# AT89S52-POV_Stick.net
KiCad netlist of a schematic drawn in EAGLE
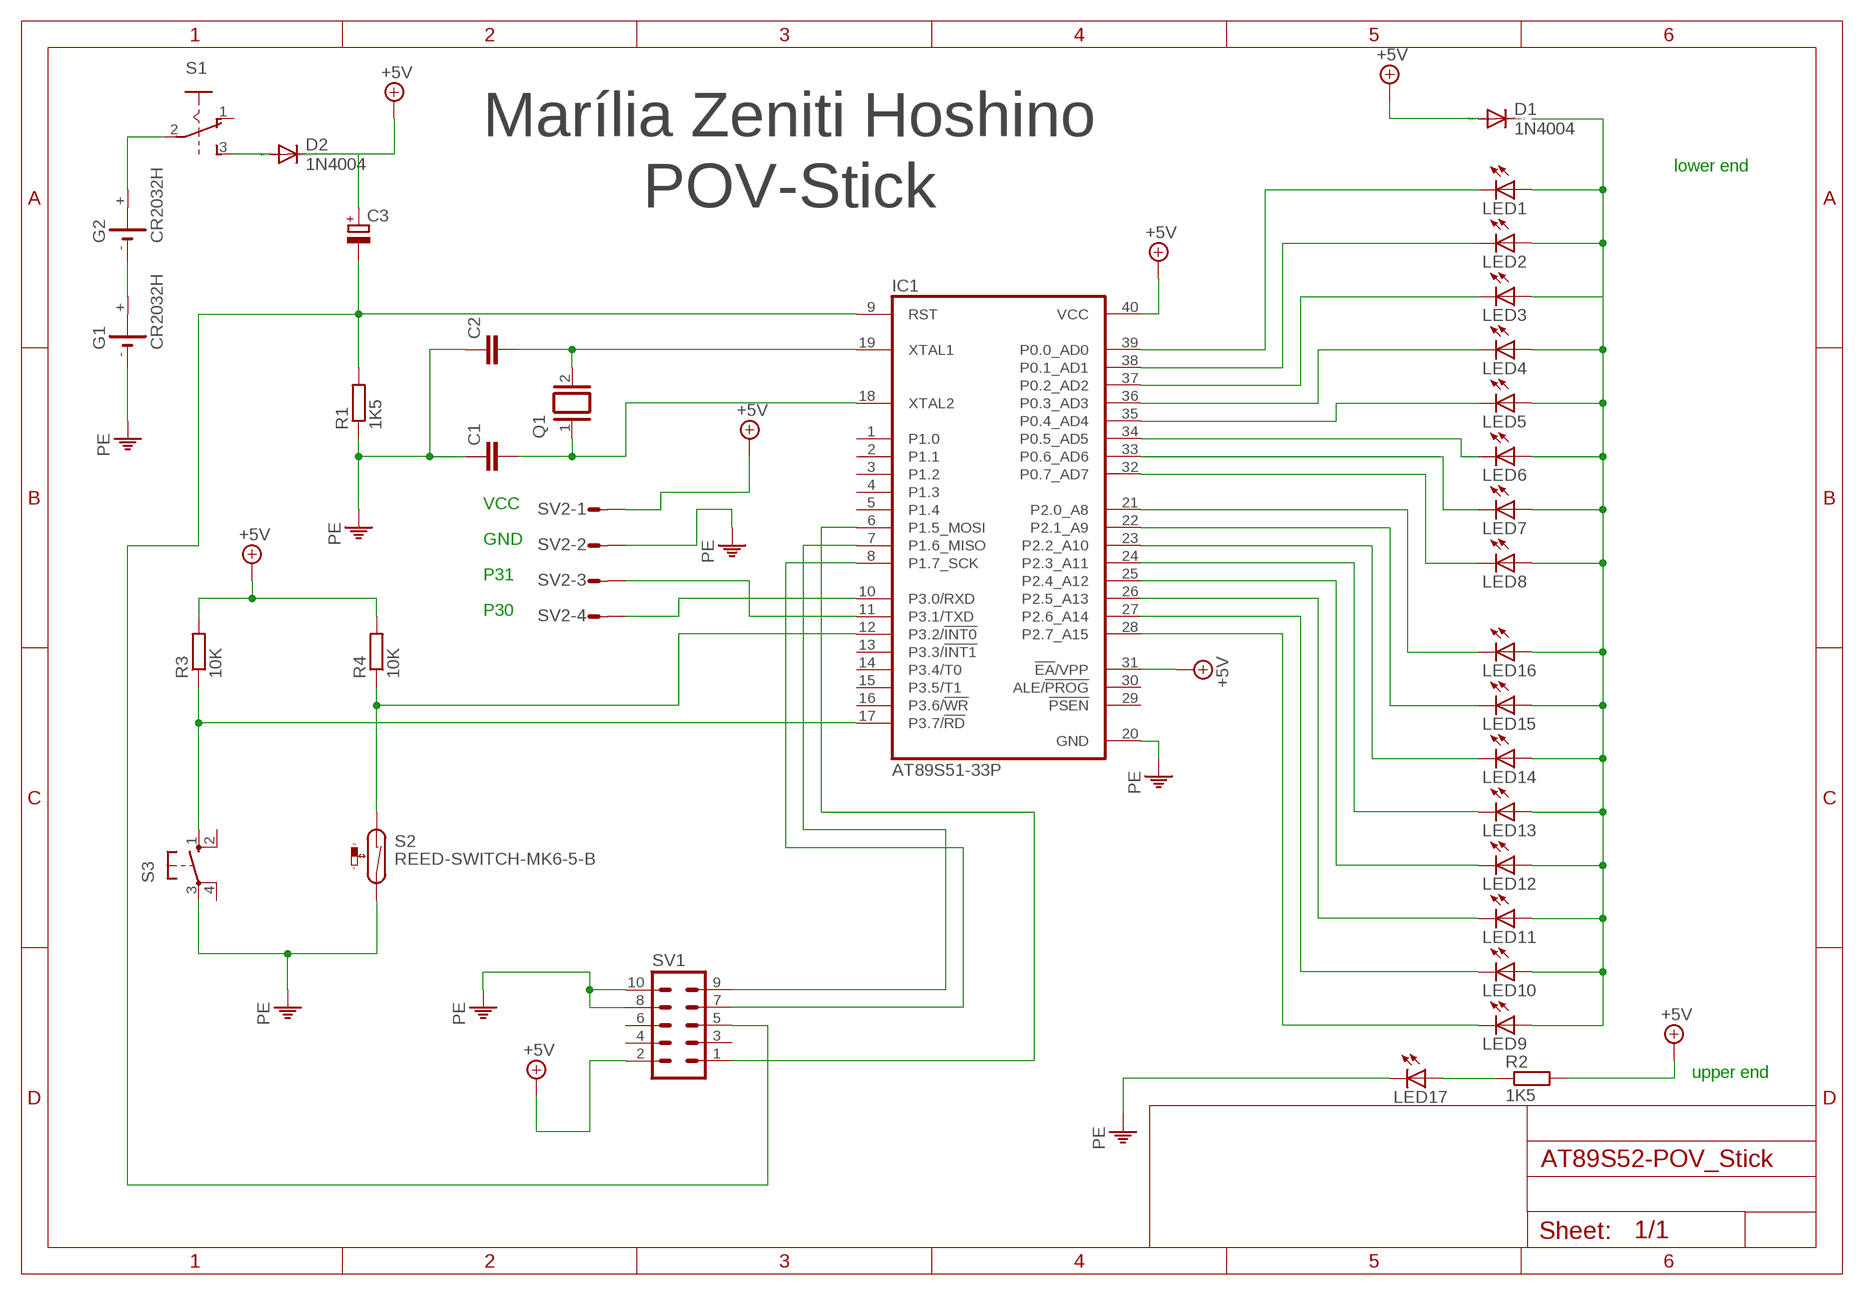
[diagram p0: schematic, sheet 1]

(export (version "E")
  (design (tool "Eeschema 10.0.6"))
  (components
    (comp (ref "C1")
      (value "C-EU025-024X044")
      (footprint "eagle-import:C025-024X044")
      (libsource (lib "eagle-import") (part "C-EU025-024X044"))
    )
    (comp (ref "C2")
      (value "C-EU025-024X044")
      (footprint "eagle-import:C025-024X044")
      (libsource (lib "eagle-import") (part "C-EU025-024X044"))
    )
    (comp (ref "C3")
      (value "CPOL-EUE2-5")
      (footprint "eagle-import:E2-5")
      (libsource (lib "eagle-import") (part "CPOL-EUE2-5"))
    )
    (comp (ref "D1")
      (value "1N4004")
      (footprint "eagle-import:DO41-10")
      (libsource (lib "eagle-import") (part "1N4004"))
    )
    (comp (ref "D2")
      (value "1N4004")
      (footprint "eagle-import:DO41-10")
      (libsource (lib "eagle-import") (part "1N4004"))
    )
    (comp (ref "G1")
      (value "CR2032H")
      (footprint "eagle-import:CR2032H")
      (libsource (lib "eagle-import") (part "CR2032H"))
    )
    (comp (ref "G2")
      (value "CR2032H")
      (footprint "eagle-import:CR2032H")
      (libsource (lib "eagle-import") (part "CR2032H"))
    )
    (comp (ref "IC1")
      (value "AT89S51-33P")
      (footprint "eagle-import:DIL40")
      (fields (field (name "MPN") "AT89S51-24PU"))
      (libsource (lib "eagle-import") (part "AT89S51-P33"))
    )
    (comp (ref "LED1")
      (value "LED5MM")
      (footprint "eagle-import:LED5MM")
      (libsource (lib "eagle-import") (part "LED5MM"))
    )
    (comp (ref "LED2")
      (value "LED5MM")
      (footprint "eagle-import:LED5MM")
      (libsource (lib "eagle-import") (part "LED5MM"))
    )
    (comp (ref "LED3")
      (value "LED5MM")
      (footprint "eagle-import:LED5MM")
      (libsource (lib "eagle-import") (part "LED5MM"))
    )
    (comp (ref "LED4")
      (value "LED5MM")
      (footprint "eagle-import:LED5MM")
      (libsource (lib "eagle-import") (part "LED5MM"))
    )
    (comp (ref "LED5")
      (value "LED5MM")
      (footprint "eagle-import:LED5MM")
      (libsource (lib "eagle-import") (part "LED5MM"))
    )
    (comp (ref "LED6")
      (value "LED5MM")
      (footprint "eagle-import:LED5MM")
      (libsource (lib "eagle-import") (part "LED5MM"))
    )
    (comp (ref "LED7")
      (value "LED5MM")
      (footprint "eagle-import:LED5MM")
      (libsource (lib "eagle-import") (part "LED5MM"))
    )
    (comp (ref "LED8")
      (value "LED5MM")
      (footprint "eagle-import:LED5MM")
      (libsource (lib "eagle-import") (part "LED5MM"))
    )
    (comp (ref "LED9")
      (value "LED5MM")
      (footprint "eagle-import:LED5MM")
      (libsource (lib "eagle-import") (part "LED5MM"))
    )
    (comp (ref "LED10")
      (value "LED5MM")
      (footprint "eagle-import:LED5MM")
      (libsource (lib "eagle-import") (part "LED5MM"))
    )
    (comp (ref "LED11")
      (value "LED5MM")
      (footprint "eagle-import:LED5MM")
      (libsource (lib "eagle-import") (part "LED5MM"))
    )
    (comp (ref "LED12")
      (value "LED5MM")
      (footprint "eagle-import:LED5MM")
      (libsource (lib "eagle-import") (part "LED5MM"))
    )
    (comp (ref "LED13")
      (value "LED5MM")
      (footprint "eagle-import:LED5MM")
      (libsource (lib "eagle-import") (part "LED5MM"))
    )
    (comp (ref "LED14")
      (value "LED5MM")
      (footprint "eagle-import:LED5MM")
      (libsource (lib "eagle-import") (part "LED5MM"))
    )
    (comp (ref "LED15")
      (value "LED5MM")
      (footprint "eagle-import:LED5MM")
      (libsource (lib "eagle-import") (part "LED5MM"))
    )
    (comp (ref "LED16")
      (value "LED5MM")
      (footprint "eagle-import:LED5MM")
      (libsource (lib "eagle-import") (part "LED5MM"))
    )
    (comp (ref "LED17")
      (value "LED5MM")
      (footprint "eagle-import:LED5MM")
      (libsource (lib "eagle-import") (part "LED5MM"))
    )
    (comp (ref "Q1")
      (value "XTAL/S")
      (footprint "eagle-import:QS")
      (libsource (lib "eagle-import") (part "XTAL/S"))
    )
    (comp (ref "R1")
      (value "1K5")
      (footprint "eagle-import:0204_7")
      (libsource (lib "eagle-import") (part "R-EU_0204/7"))
    )
    (comp (ref "R2")
      (value "1K5")
      (footprint "eagle-import:0204_7")
      (libsource (lib "eagle-import") (part "R-EU_0204/7"))
    )
    (comp (ref "R3")
      (value "10K")
      (footprint "eagle-import:0204_7")
      (libsource (lib "eagle-import") (part "R-EU_0204/7"))
    )
    (comp (ref "R4")
      (value "10K")
      (footprint "eagle-import:0204_7")
      (libsource (lib "eagle-import") (part "R-EU_0204/7"))
    )
    (comp (ref "S1")
      (value "A68-A31")
      (footprint "eagle-import:A68-A31")
      (libsource (lib "eagle-import") (part "A68-A31"))
    )
    (comp (ref "S2")
      (value "REED-SWITCH-MK6-5-B")
      (footprint "eagle-import:MK6-5")
      (fields (field (name "MF") "MEDER") (field (name "MPN") "MK6-5-B"))
      (libsource (lib "eagle-import") (part "REED-SWITCH-MK6-5-B"))
    )
    (comp (ref "S3")
      (value "10-XX")
      (footprint "eagle-import:B3F-10XX")
      (fields (field (name "MPN") "B3F-1000"))
      (libsource (lib "eagle-import") (part "10-XX"))
    )
    (comp (ref "SV1")
      (value "ML10")
      (footprint "eagle-import:ML10")
      (libsource (lib "eagle-import") (part "ML10"))
    )
    (comp (ref "SV2")
      (value "S04P")
      (footprint "eagle-import:S04P")
      (libsource (lib "eagle-import") (part "S04P"))
    )
  )
  (nets
    (net (code "1") (name "+5V") (class "Default")
      (node (ref "C3") (pin "+") (pinfunction "+_+") (pintype "passive"))
      (node (ref "D1") (pin "A") (pinfunction "A_A") (pintype "passive"))
      (node (ref "D2") (pin "C") (pinfunction "C_C") (pintype "passive"))
      (node (ref "IC1") (pin "31") (pinfunction "~{EA}/VPP_31") (pintype "input"))
      (node (ref "IC1") (pin "40") (pinfunction "VCC_40") (pintype "power_in"))
      (node (ref "R2") (pin "2") (pinfunction "2_2") (pintype "passive"))
      (node (ref "R3") (pin "2") (pinfunction "2_2") (pintype "passive"))
      (node (ref "R4") (pin "2") (pinfunction "2_2") (pintype "passive"))
      (node (ref "SV1") (pin "2") (pinfunction "2_2") (pintype "passive"))
      (node (ref "SV2") (pin "1") (pinfunction "S_1") (pintype "passive"))
    )
    (net (code "2") (name "Net-(G1-Pad+)") (class "Default")
      (node (ref "G1") (pin "+") (pinfunction "+_+") (pintype "passive"))
      (node (ref "G2") (pin "-") (pinfunction "-_-") (pintype "passive"))
    )
    (net (code "3") (name "Net-(IC1-P0.0_AD0)") (class "Default")
      (node (ref "IC1") (pin "39") (pinfunction "P0.0_AD0_39") (pintype "bidirectional"))
      (node (ref "LED1") (pin "K") (pinfunction "C_K") (pintype "passive"))
    )
    (net (code "4") (name "Net-(IC1-P0.1_AD1)") (class "Default")
      (node (ref "IC1") (pin "38") (pinfunction "P0.1_AD1_38") (pintype "bidirectional"))
      (node (ref "LED2") (pin "K") (pinfunction "C_K") (pintype "passive"))
    )
    (net (code "5") (name "Net-(IC1-P0.2_AD2)") (class "Default")
      (node (ref "IC1") (pin "37") (pinfunction "P0.2_AD2_37") (pintype "bidirectional"))
      (node (ref "LED3") (pin "K") (pinfunction "C_K") (pintype "passive"))
    )
    (net (code "6") (name "Net-(IC1-P0.3_AD3)") (class "Default")
      (node (ref "IC1") (pin "36") (pinfunction "P0.3_AD3_36") (pintype "bidirectional"))
      (node (ref "LED4") (pin "K") (pinfunction "C_K") (pintype "passive"))
    )
    (net (code "7") (name "Net-(IC1-P0.4_AD4)") (class "Default")
      (node (ref "IC1") (pin "35") (pinfunction "P0.4_AD4_35") (pintype "bidirectional"))
      (node (ref "LED5") (pin "K") (pinfunction "C_K") (pintype "passive"))
    )
    (net (code "8") (name "Net-(IC1-P0.5_AD5)") (class "Default")
      (node (ref "IC1") (pin "34") (pinfunction "P0.5_AD5_34") (pintype "bidirectional"))
      (node (ref "LED6") (pin "K") (pinfunction "C_K") (pintype "passive"))
    )
    (net (code "9") (name "Net-(IC1-P0.6_AD6)") (class "Default")
      (node (ref "IC1") (pin "33") (pinfunction "P0.6_AD6_33") (pintype "bidirectional"))
      (node (ref "LED7") (pin "K") (pinfunction "C_K") (pintype "passive"))
    )
    (net (code "10") (name "Net-(IC1-P0.7_AD7)") (class "Default")
      (node (ref "IC1") (pin "32") (pinfunction "P0.7_AD7_32") (pintype "bidirectional"))
      (node (ref "LED8") (pin "K") (pinfunction "C_K") (pintype "passive"))
    )
    (net (code "11") (name "Net-(IC1-P1.5_MOSI)") (class "Default")
      (node (ref "IC1") (pin "6") (pinfunction "P1.5_MOSI_6") (pintype "bidirectional"))
      (node (ref "SV1") (pin "1") (pinfunction "1_1") (pintype "passive"))
    )
    (net (code "12") (name "Net-(IC1-P1.6_MISO)") (class "Default")
      (node (ref "IC1") (pin "7") (pinfunction "P1.6_MISO_7") (pintype "bidirectional"))
      (node (ref "SV1") (pin "9") (pinfunction "9_9") (pintype "passive"))
    )
    (net (code "13") (name "Net-(IC1-P1.7_SCK)") (class "Default")
      (node (ref "IC1") (pin "8") (pinfunction "P1.7_SCK_8") (pintype "bidirectional"))
      (node (ref "SV1") (pin "7") (pinfunction "7_7") (pintype "passive"))
    )
    (net (code "14") (name "Net-(IC1-P2.0_A8)") (class "Default")
      (node (ref "IC1") (pin "21") (pinfunction "P2.0_A8_21") (pintype "bidirectional"))
      (node (ref "LED16") (pin "K") (pinfunction "C_K") (pintype "passive"))
    )
    (net (code "15") (name "Net-(IC1-P2.1_A9)") (class "Default")
      (node (ref "IC1") (pin "22") (pinfunction "P2.1_A9_22") (pintype "bidirectional"))
      (node (ref "LED15") (pin "K") (pinfunction "C_K") (pintype "passive"))
    )
    (net (code "16") (name "Net-(IC1-P2.2_A10)") (class "Default")
      (node (ref "IC1") (pin "23") (pinfunction "P2.2_A10_23") (pintype "bidirectional"))
      (node (ref "LED14") (pin "K") (pinfunction "C_K") (pintype "passive"))
    )
    (net (code "17") (name "Net-(IC1-P2.3_A11)") (class "Default")
      (node (ref "IC1") (pin "24") (pinfunction "P2.3_A11_24") (pintype "bidirectional"))
      (node (ref "LED13") (pin "K") (pinfunction "C_K") (pintype "passive"))
    )
    (net (code "18") (name "Net-(IC1-P2.4_A12)") (class "Default")
      (node (ref "IC1") (pin "25") (pinfunction "P2.4_A12_25") (pintype "bidirectional"))
      (node (ref "LED12") (pin "K") (pinfunction "C_K") (pintype "passive"))
    )
    (net (code "19") (name "Net-(IC1-P2.5_A13)") (class "Default")
      (node (ref "IC1") (pin "26") (pinfunction "P2.5_A13_26") (pintype "bidirectional"))
      (node (ref "LED11") (pin "K") (pinfunction "C_K") (pintype "passive"))
    )
    (net (code "20") (name "Net-(IC1-P2.6_A14)") (class "Default")
      (node (ref "IC1") (pin "27") (pinfunction "P2.6_A14_27") (pintype "bidirectional"))
      (node (ref "LED10") (pin "K") (pinfunction "C_K") (pintype "passive"))
    )
    (net (code "21") (name "Net-(IC1-P2.7_A15)") (class "Default")
      (node (ref "IC1") (pin "28") (pinfunction "P2.7_A15_28") (pintype "bidirectional"))
      (node (ref "LED9") (pin "K") (pinfunction "C_K") (pintype "passive"))
    )
    (net (code "22") (name "Net-(IC1-P3.0{slash}RXD)") (class "Default")
      (node (ref "IC1") (pin "10") (pinfunction "P3.0/RXD_10") (pintype "bidirectional"))
      (node (ref "SV2") (pin "4") (pinfunction "S_4") (pintype "passive"))
    )
    (net (code "23") (name "Net-(IC1-P3.1{slash}TXD)") (class "Default")
      (node (ref "IC1") (pin "11") (pinfunction "P3.1/TXD_11") (pintype "bidirectional"))
      (node (ref "SV2") (pin "3") (pinfunction "S_3") (pintype "passive"))
    )
    (net (code "24") (name "Net-(IC1-P3.2{slash}~{INT0})") (class "Default")
      (node (ref "IC1") (pin "12") (pinfunction "P3.2/~{INT0}_12") (pintype "bidirectional"))
      (node (ref "R4") (pin "1") (pinfunction "1_1") (pintype "passive"))
      (node (ref "S2") (pin "1") (pinfunction "1_1") (pintype "passive"))
    )
    (net (code "25") (name "Net-(IC1-P3.7{slash}~{RD})") (class "Default")
      (node (ref "IC1") (pin "17") (pinfunction "P3.7/~{RD}_17") (pintype "bidirectional"))
      (node (ref "R3") (pin "1") (pinfunction "1_1") (pintype "passive"))
      (node (ref "S3") (pin "1") (pinfunction "S_1") (pintype "passive"))
    )
    (net (code "26") (name "Net-(IC1-RST)") (class "Default")
      (node (ref "C3") (pin "-") (pinfunction "-_-") (pintype "passive"))
      (node (ref "IC1") (pin "9") (pinfunction "RST_9") (pintype "input"))
      (node (ref "R1") (pin "2") (pinfunction "2_2") (pintype "passive"))
      (node (ref "SV1") (pin "5") (pinfunction "5_5") (pintype "passive"))
    )
    (net (code "27") (name "Net-(IC1-XTAL1)") (class "Default")
      (node (ref "C2") (pin "2") (pinfunction "2_2") (pintype "passive"))
      (node (ref "IC1") (pin "19") (pinfunction "XTAL1_19") (pintype "input"))
      (node (ref "Q1") (pin "2") (pinfunction "2_2") (pintype "passive"))
    )
    (net (code "28") (name "Net-(IC1-XTAL2)") (class "Default")
      (node (ref "C1") (pin "2") (pinfunction "2_2") (pintype "passive"))
      (node (ref "IC1") (pin "18") (pinfunction "XTAL2_18") (pintype "input"))
      (node (ref "Q1") (pin "1") (pinfunction "1_1") (pintype "passive"))
    )
    (net (code "29") (name "Net-(LED1-PadA)") (class "Default")
      (node (ref "LED1") (pin "A") (pinfunction "A_A") (pintype "passive"))
      (node (ref "LED10") (pin "A") (pinfunction "A_A") (pintype "passive"))
      (node (ref "LED11") (pin "A") (pinfunction "A_A") (pintype "passive"))
      (node (ref "LED12") (pin "A") (pinfunction "A_A") (pintype "passive"))
      (node (ref "LED13") (pin "A") (pinfunction "A_A") (pintype "passive"))
      (node (ref "LED14") (pin "A") (pinfunction "A_A") (pintype "passive"))
      (node (ref "LED15") (pin "A") (pinfunction "A_A") (pintype "passive"))
      (node (ref "LED16") (pin "A") (pinfunction "A_A") (pintype "passive"))
      (node (ref "LED2") (pin "A") (pinfunction "A_A") (pintype "passive"))
      (node (ref "LED3") (pin "A") (pinfunction "A_A") (pintype "passive"))
      (node (ref "LED4") (pin "A") (pinfunction "A_A") (pintype "passive"))
      (node (ref "LED5") (pin "A") (pinfunction "A_A") (pintype "passive"))
      (node (ref "LED6") (pin "A") (pinfunction "A_A") (pintype "passive"))
      (node (ref "LED7") (pin "A") (pinfunction "A_A") (pintype "passive"))
      (node (ref "LED8") (pin "A") (pinfunction "A_A") (pintype "passive"))
      (node (ref "LED9") (pin "A") (pinfunction "A_A") (pintype "passive"))
    )
    (net (code "30") (name "Net-(LED17-PadA)") (class "Default")
      (node (ref "LED17") (pin "A") (pinfunction "A_A") (pintype "passive"))
      (node (ref "R2") (pin "1") (pinfunction "1_1") (pintype "passive"))
    )
    (net (code "31") (name "Net-(S1A-P)") (class "Default")
      (node (ref "G2") (pin "+") (pinfunction "+_+") (pintype "passive"))
      (node (ref "S1") (pin "2") (pinfunction "P_2") (pintype "passive"))
    )
    (net (code "32") (name "Net-(S1A-S)") (class "Default")
      (node (ref "D2") (pin "A") (pinfunction "A_A") (pintype "passive"))
      (node (ref "S1") (pin "3") (pinfunction "S_3") (pintype "passive"))
    )
    (net (code "33") (name "PE") (class "Default")
      (node (ref "C1") (pin "1") (pinfunction "1_1") (pintype "passive"))
      (node (ref "C2") (pin "1") (pinfunction "1_1") (pintype "passive"))
      (node (ref "G1") (pin "-") (pinfunction "-_-") (pintype "passive"))
      (node (ref "IC1") (pin "20") (pinfunction "GND_20") (pintype "power_in"))
      (node (ref "LED17") (pin "K") (pinfunction "C_K") (pintype "passive"))
      (node (ref "R1") (pin "1") (pinfunction "1_1") (pintype "passive"))
      (node (ref "S2") (pin "2") (pinfunction "2_2") (pintype "passive"))
      (node (ref "S3") (pin "3") (pinfunction "P_3") (pintype "passive"))
      (node (ref "SV1") (pin "10") (pinfunction "10_10") (pintype "passive"))
      (node (ref "SV1") (pin "8") (pinfunction "8_8") (pintype "passive"))
      (node (ref "SV2") (pin "2") (pinfunction "S_2") (pintype "passive"))
    )
    (net (code "34") (name "unconnected-(D1-PadC)") (class "Default")
      (node (ref "D1") (pin "C") (pinfunction "C_C") (pintype "passive"))
    )
    (net (code "35") (name "unconnected-(G1-+-Pad+@1)") (class "Default")
      (node (ref "G1") (pin "+@1") (pinfunction "+_+@1") (pintype "passive"))
    )
    (net (code "36") (name "unconnected-(G2-+-Pad+@1)") (class "Default")
      (node (ref "G2") (pin "+@1") (pinfunction "+_+@1") (pintype "passive"))
    )
    (net (code "37") (name "unconnected-(IC1-ALE{slash}~{PROG}-Pad30)") (class "Default")
      (node (ref "IC1") (pin "30") (pinfunction "ALE/~{PROG}_30") (pintype "output"))
    )
    (net (code "38") (name "unconnected-(IC1-P1.0-Pad1)") (class "Default")
      (node (ref "IC1") (pin "1") (pinfunction "P1.0_1") (pintype "bidirectional"))
    )
    (net (code "39") (name "unconnected-(IC1-P1.1-Pad2)") (class "Default")
      (node (ref "IC1") (pin "2") (pinfunction "P1.1_2") (pintype "bidirectional"))
    )
    (net (code "40") (name "unconnected-(IC1-P1.2-Pad3)") (class "Default")
      (node (ref "IC1") (pin "3") (pinfunction "P1.2_3") (pintype "bidirectional"))
    )
    (net (code "41") (name "unconnected-(IC1-P1.3-Pad4)") (class "Default")
      (node (ref "IC1") (pin "4") (pinfunction "P1.3_4") (pintype "bidirectional"))
    )
    (net (code "42") (name "unconnected-(IC1-P1.4-Pad5)") (class "Default")
      (node (ref "IC1") (pin "5") (pinfunction "P1.4_5") (pintype "bidirectional"))
    )
    (net (code "43") (name "unconnected-(IC1-P3.3{slash}~{INT1}-Pad13)") (class "Default")
      (node (ref "IC1") (pin "13") (pinfunction "P3.3/~{INT1}_13") (pintype "bidirectional"))
    )
    (net (code "44") (name "unconnected-(IC1-P3.4{slash}T0-Pad14)") (class "Default")
      (node (ref "IC1") (pin "14") (pinfunction "P3.4/T0_14") (pintype "bidirectional"))
    )
    (net (code "45") (name "unconnected-(IC1-P3.5{slash}T1-Pad15)") (class "Default")
      (node (ref "IC1") (pin "15") (pinfunction "P3.5/T1_15") (pintype "bidirectional"))
    )
    (net (code "46") (name "unconnected-(IC1-P3.6{slash}~{WR}-Pad16)") (class "Default")
      (node (ref "IC1") (pin "16") (pinfunction "P3.6/~{WR}_16") (pintype "bidirectional"))
    )
    (net (code "47") (name "unconnected-(IC1-~{PSEN}-Pad29)") (class "Default")
      (node (ref "IC1") (pin "29") (pinfunction "~{PSEN}_29") (pintype "output"))
    )
    (net (code "48") (name "unconnected-(S1A-O-Pad1)") (class "Default")
      (node (ref "S1") (pin "1") (pinfunction "O_1") (pintype "passive"))
    )
    (net (code "49") (name "unconnected-(S3-P1-Pad4)") (class "Default")
      (node (ref "S3") (pin "4") (pinfunction "P1_4") (pintype "passive"))
    )
    (net (code "50") (name "unconnected-(S3-S1-Pad2)") (class "Default")
      (node (ref "S3") (pin "2") (pinfunction "S1_2") (pintype "passive"))
    )
    (net (code "51") (name "unconnected-(SV1-Pad3)") (class "Default")
      (node (ref "SV1") (pin "3") (pinfunction "3_3") (pintype "passive"))
    )
    (net (code "52") (name "unconnected-(SV1-Pad4)") (class "Default")
      (node (ref "SV1") (pin "4") (pinfunction "4_4") (pintype "passive"))
    )
    (net (code "53") (name "unconnected-(SV1-Pad6)") (class "Default")
      (node (ref "SV1") (pin "6") (pinfunction "6_6") (pintype "passive"))
    )
  )
)
